# High_Precision_Laboratory_Voltage_Calibr.net
KiCad netlist of a schematic drawn in Altium Designer
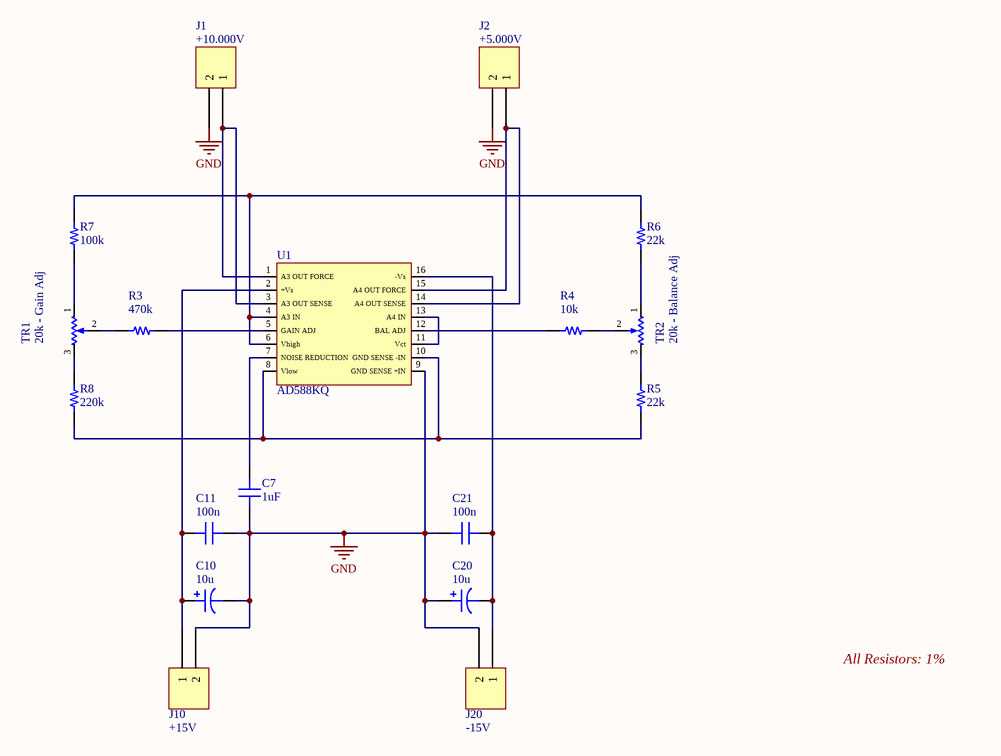
[diagram p0: High Precision Laboratory Voltage Calibrator.SchDoc]

(export (version "E")
  (design (tool "Eeschema 10.0.6"))
  (components
    (comp (ref "C7")
      (value "1uF")
      (footprint "CAP 0805/2012")
      (description "SMT Capacitor")
      (libsource (lib "SMD Passive Components") (part "Capacitor"))
    )
    (comp (ref "C10")
      (value "10u")
      (footprint "RB.2/.4-CAP-POL")
      (description "RAD Polarised Capacitor")
      (libsource (lib "THD Passive Components") (part "Capacitor POL RAD"))
    )
    (comp (ref "C11")
      (value "100n")
      (footprint "CAP 0805/2012")
      (description "SMT Capacitor")
      (libsource (lib "SMD Passive Components") (part "Capacitor"))
    )
    (comp (ref "C20")
      (value "10u")
      (footprint "RB.2/.4-CAP-POL")
      (description "RAD Polarised Capacitor")
      (libsource (lib "THD Passive Components") (part "Capacitor POL RAD"))
    )
    (comp (ref "C21")
      (value "100n")
      (footprint "CAP 0805/2012")
      (description "SMT Capacitor")
      (libsource (lib "SMD Passive Components") (part "Capacitor"))
    )
    (comp (ref "J1")
      (value "+10.000V")
      (footprint "SAMTEC SSW-102-03-T-S")
      (libsource (lib "THD Connectors") (part "1x2 Pin Header - SAMTEC SULLINS"))
    )
    (comp (ref "J2")
      (value "+5.000V")
      (footprint "SAMTEC SSW-102-03-T-S")
      (libsource (lib "THD Connectors") (part "1x2 Pin Header - SAMTEC SULLINS"))
    )
    (comp (ref "J10")
      (value "+15V")
      (footprint "SAMTEC SSW-102-03-T-S")
      (libsource (lib "") (part "1x2 Pin Header - SAMTEC SULLINS_2"))
    )
    (comp (ref "J20")
      (value "-15V")
      (footprint "SAMTEC SSW-102-03-T-S")
      (libsource (lib "") (part "1x2 Pin Header - SAMTEC SULLINS_1"))
    )
    (comp (ref "R3")
      (value "470k")
      (footprint "RES 0805/2012")
      (description "SMT Resistor")
      (libsource (lib "SMD Passive Components") (part "Resistor"))
    )
    (comp (ref "R4")
      (value "10k")
      (footprint "RES 0805/2012")
      (description "SMT Resistor")
      (libsource (lib "SMD Passive Components") (part "Resistor"))
    )
    (comp (ref "R5")
      (value "22k")
      (footprint "RES 0805/2012")
      (description "SMT Resistor")
      (libsource (lib "SMD Passive Components") (part "Resistor"))
    )
    (comp (ref "R6")
      (value "22k")
      (footprint "RES 0805/2012")
      (description "SMT Resistor")
      (libsource (lib "SMD Passive Components") (part "Resistor"))
    )
    (comp (ref "R7")
      (value "100k")
      (footprint "RES 0805/2012")
      (description "SMT Resistor")
      (libsource (lib "SMD Passive Components") (part "Resistor"))
    )
    (comp (ref "R8")
      (value "220k")
      (footprint "RES 0805/2012")
      (description "SMT Resistor")
      (libsource (lib "SMD Passive Components") (part "Resistor"))
    )
    (comp (ref "TR1")
      (value "20k - Gain Adj")
      (footprint "Bourns 3296w")
      (description "Trimmers 1")
      (libsource (lib "THD Passive Components") (part "Trimmers 1"))
    )
    (comp (ref "TR2")
      (value "20k - Balance Adj")
      (footprint "Bourns 3296w")
      (description "Trimmers 1")
      (libsource (lib "THD Passive Components") (part "Trimmers 1"))
    )
    (comp (ref "U1")
      (value "AD588KQ")
      (footprint "DIP16-300")
      (description "Multiple Output, High Precision,\r\nDual-Tracking Reference")
      (libsource (lib "THD Voltage Reference and Regulators") (part "AD588KQ"))
    )
  )
  (nets
    (net (code "1") (name "GND") (class "Default")
      (node (ref "C10") (pin "2") (pinfunction "2_2") (pintype "passive"))
      (node (ref "C11") (pin "1") (pinfunction "1_1") (pintype "passive"))
      (node (ref "C20") (pin "1") (pinfunction "1_1") (pintype "passive"))
      (node (ref "C21") (pin "2") (pinfunction "2_2") (pintype "passive"))
      (node (ref "C7") (pin "1") (pinfunction "1_1") (pintype "passive"))
      (node (ref "J1") (pin "2") (pinfunction "2_2") (pintype "passive"))
      (node (ref "J10") (pin "2") (pinfunction "2_2") (pintype "passive"))
      (node (ref "J2") (pin "2") (pinfunction "2_2") (pintype "passive"))
      (node (ref "J20") (pin "2") (pinfunction "2_2") (pintype "passive"))
      (node (ref "U1") (pin "9") (pinfunction "GND_SENSE_+IN_9") (pintype "passive"))
    )
    (net (code "2") (name "Net-(R3-Pad2)") (class "Default")
      (node (ref "R3") (pin "2") (pinfunction "2_2") (pintype "passive"))
      (node (ref "TR1") (pin "2") (pinfunction "2_2") (pintype "passive"))
    )
    (net (code "3") (name "Net-(R4-Pad1)") (class "Default")
      (node (ref "R4") (pin "1") (pinfunction "1_1") (pintype "passive"))
      (node (ref "TR2") (pin "2") (pinfunction "2_2") (pintype "passive"))
    )
    (net (code "4") (name "Net-(R5-Pad2)") (class "Default")
      (node (ref "R5") (pin "2") (pinfunction "2_2") (pintype "passive"))
      (node (ref "TR2") (pin "3") (pinfunction "3_3") (pintype "passive"))
    )
    (net (code "5") (name "Net-(R6-Pad1)") (class "Default")
      (node (ref "R6") (pin "1") (pinfunction "1_1") (pintype "passive"))
      (node (ref "TR2") (pin "1") (pinfunction "1_1") (pintype "passive"))
    )
    (net (code "6") (name "Net-(R7-Pad1)") (class "Default")
      (node (ref "R7") (pin "1") (pinfunction "1_1") (pintype "passive"))
      (node (ref "TR1") (pin "1") (pinfunction "1_1") (pintype "passive"))
    )
    (net (code "7") (name "Net-(R8-Pad2)") (class "Default")
      (node (ref "R8") (pin "2") (pinfunction "2_2") (pintype "passive"))
      (node (ref "TR1") (pin "3") (pinfunction "3_3") (pintype "passive"))
    )
    (net (code "8") (name "Net-(U1-+Vs)") (class "Default")
      (node (ref "C10") (pin "1") (pinfunction "1_1") (pintype "passive"))
      (node (ref "C11") (pin "2") (pinfunction "2_2") (pintype "passive"))
      (node (ref "J10") (pin "1") (pinfunction "1_1") (pintype "passive"))
      (node (ref "U1") (pin "2") (pinfunction "+Vs_2") (pintype "passive"))
    )
    (net (code "9") (name "Net-(U1--Vs)") (class "Default")
      (node (ref "C20") (pin "2") (pinfunction "2_2") (pintype "passive"))
      (node (ref "C21") (pin "1") (pinfunction "1_1") (pintype "passive"))
      (node (ref "J20") (pin "1") (pinfunction "1_1") (pintype "passive"))
      (node (ref "U1") (pin "16") (pinfunction "-Vs_16") (pintype "passive"))
    )
    (net (code "10") (name "Net-(U1-A3_IN)") (class "Default")
      (node (ref "R6") (pin "2") (pinfunction "2_2") (pintype "passive"))
      (node (ref "R7") (pin "2") (pinfunction "2_2") (pintype "passive"))
      (node (ref "U1") (pin "4") (pinfunction "A3_IN_4") (pintype "passive"))
      (node (ref "U1") (pin "6") (pinfunction "Vhigh_6") (pintype "passive"))
    )
    (net (code "11") (name "Net-(U1-A3_OUT_FORCE)") (class "Default")
      (node (ref "J1") (pin "1") (pinfunction "1_1") (pintype "passive"))
      (node (ref "U1") (pin "1") (pinfunction "A3_OUT_FORCE_1") (pintype "passive"))
      (node (ref "U1") (pin "3") (pinfunction "A3_OUT_SENSE_3") (pintype "passive"))
    )
    (net (code "12") (name "Net-(U1-A4_IN)") (class "Default")
      (node (ref "U1") (pin "11") (pinfunction "Vct_11") (pintype "passive"))
      (node (ref "U1") (pin "13") (pinfunction "A4_IN_13") (pintype "passive"))
    )
    (net (code "13") (name "Net-(U1-A4_OUT_FORCE)") (class "Default")
      (node (ref "J2") (pin "1") (pinfunction "1_1") (pintype "passive"))
      (node (ref "U1") (pin "14") (pinfunction "A4_OUT_SENSE_14") (pintype "passive"))
      (node (ref "U1") (pin "15") (pinfunction "A4_OUT_FORCE_15") (pintype "passive"))
    )
    (net (code "14") (name "Net-(U1-BAL_ADJ)") (class "Default")
      (node (ref "R4") (pin "2") (pinfunction "2_2") (pintype "passive"))
      (node (ref "U1") (pin "12") (pinfunction "BAL_ADJ_12") (pintype "passive"))
    )
    (net (code "15") (name "Net-(U1-GAIN_ADJ)") (class "Default")
      (node (ref "R3") (pin "1") (pinfunction "1_1") (pintype "passive"))
      (node (ref "U1") (pin "5") (pinfunction "GAIN_ADJ_5") (pintype "passive"))
    )
    (net (code "16") (name "Net-(U1-GND_SENSE_-IN)") (class "Default")
      (node (ref "R5") (pin "1") (pinfunction "1_1") (pintype "passive"))
      (node (ref "R8") (pin "1") (pinfunction "1_1") (pintype "passive"))
      (node (ref "U1") (pin "10") (pinfunction "GND_SENSE_-IN_10") (pintype "passive"))
      (node (ref "U1") (pin "8") (pinfunction "Vlow_8") (pintype "passive"))
    )
    (net (code "17") (name "Net-(U1-NOISE_REDUCTION)") (class "Default")
      (node (ref "C7") (pin "2") (pinfunction "2_2") (pintype "passive"))
      (node (ref "U1") (pin "7") (pinfunction "NOISE_REDUCTION_7") (pintype "passive"))
    )
  )
)
